# interlinkP1B.net
KiCad netlist of a schematic drawn in Altium Designer
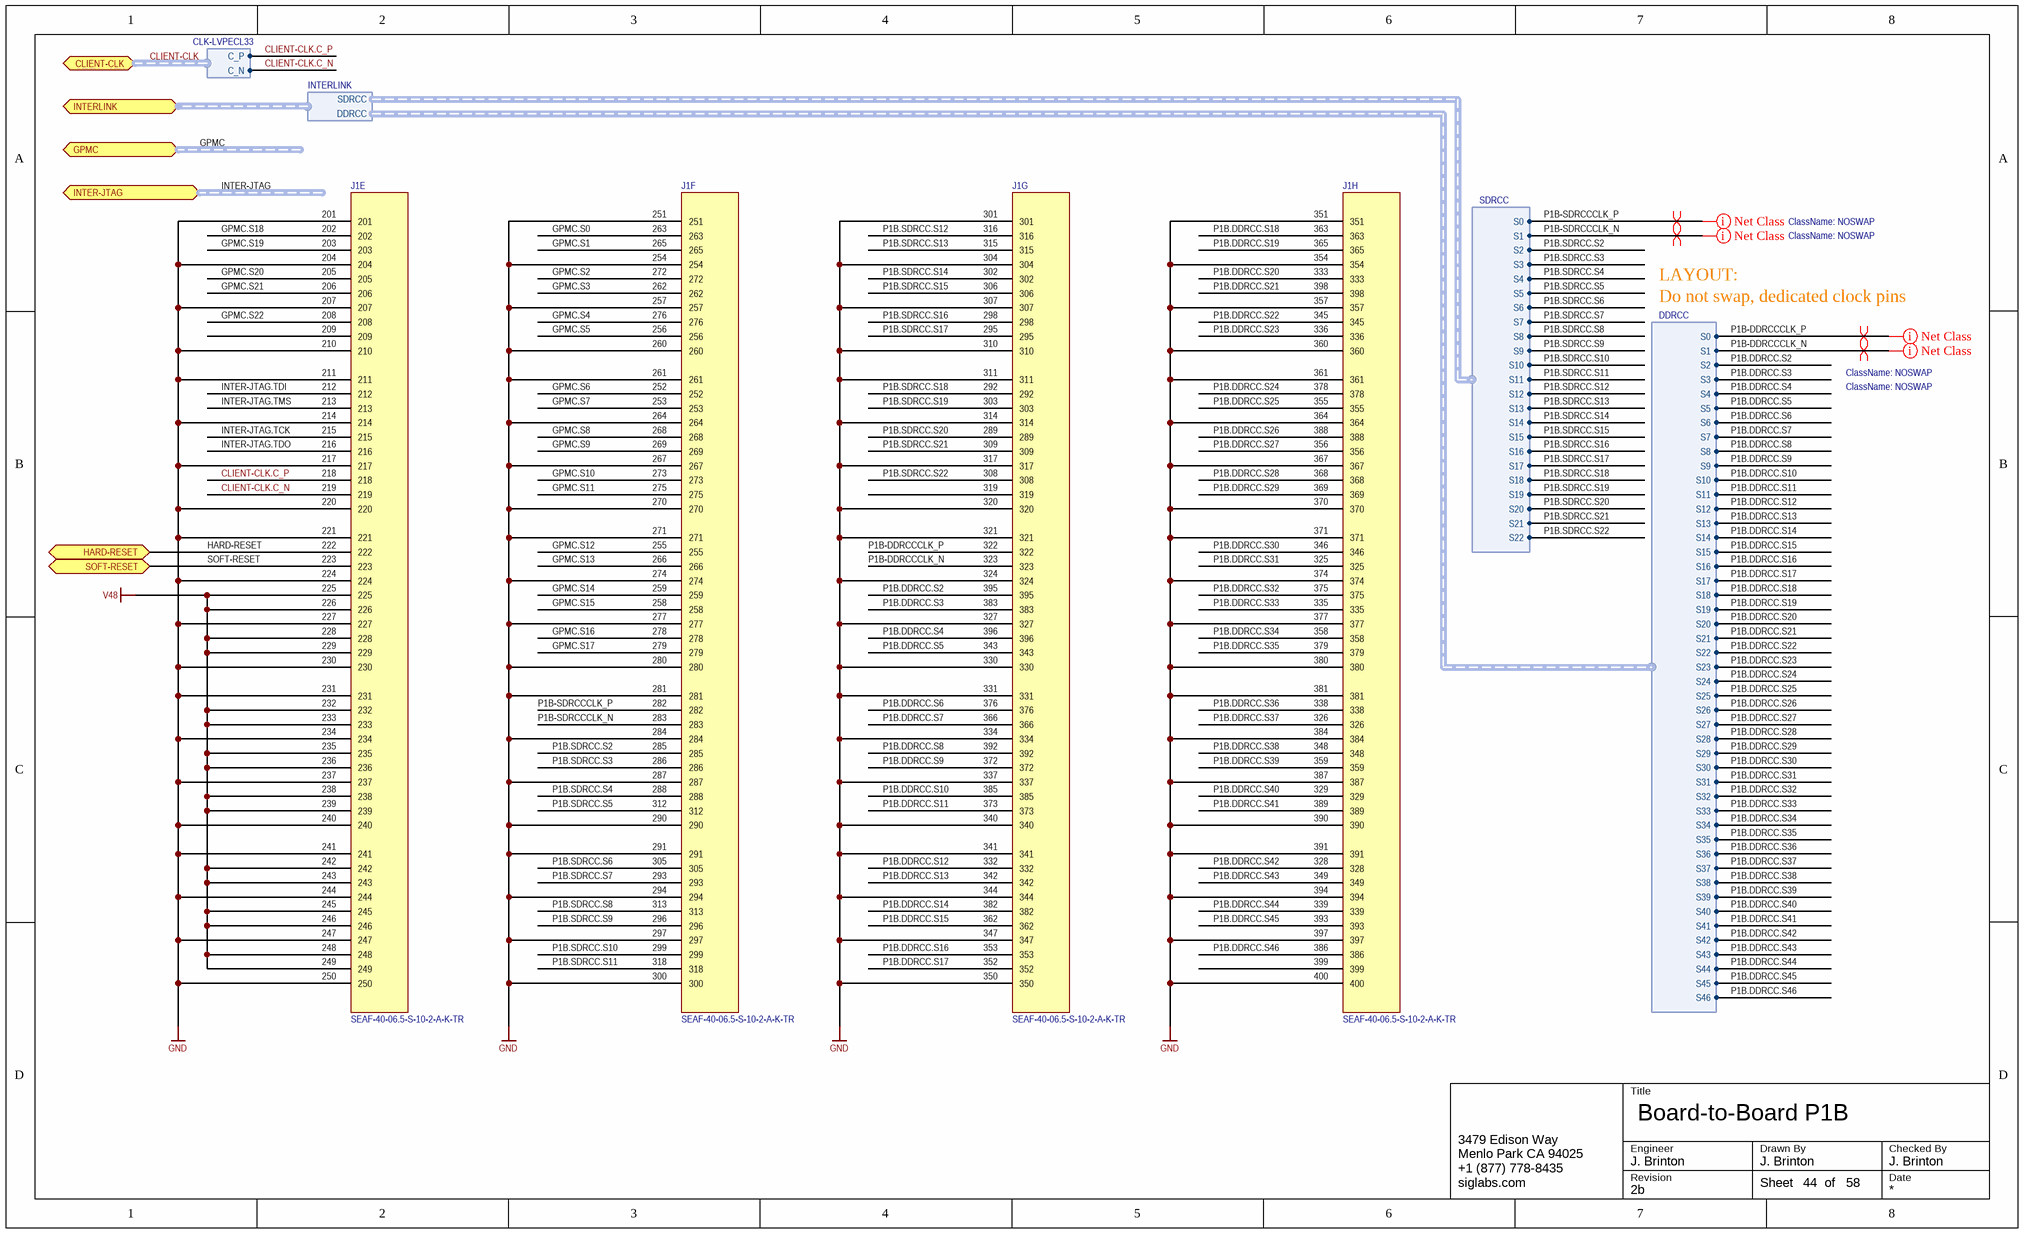
[diagram p0: interlinkP1B.SchDoc]

(export (version "E")
  (design (tool "Eeschema 10.0.6"))
  (components
    (comp (ref "J1")
      (value "SEAF-40-06.5-S-10-2-A-K-TR")
      (footprint "samtec:SEAF-40-06.5-S-10-2-A-K-TR")
      (description "Terminal Array Assembly, Surface Mount, 0.050\" Pitch, 400 Pins")
      (fields (field (name "MANUFACTURER") "Samtec"))
      (libsource (lib "") (part "SEAF-40-06.5-S-10-2-A-K-TR_1"))
    )
  )
  (nets
    (net (code "7") (name "/CLIENT-CLK.C_N") (class "Default")
      (node (ref "J1") (pin "219") (pinfunction "219_219") (pintype "passive"))
    )
    (net (code "8") (name "/CLIENT-CLK.C_P") (class "Default")
      (node (ref "J1") (pin "218") (pinfunction "218_218") (pintype "passive"))
    )
    (net (code "10") (name "/GPMC.S0") (class "Default")
      (node (ref "J1") (pin "263") (pinfunction "263_263") (pintype "passive"))
    )
    (net (code "11") (name "/GPMC.S1") (class "Default")
      (node (ref "J1") (pin "265") (pinfunction "265_265") (pintype "passive"))
    )
    (net (code "12") (name "/GPMC.S2") (class "Default")
      (node (ref "J1") (pin "272") (pinfunction "272_272") (pintype "passive"))
    )
    (net (code "13") (name "/GPMC.S3") (class "Default")
      (node (ref "J1") (pin "262") (pinfunction "262_262") (pintype "passive"))
    )
    (net (code "14") (name "/GPMC.S4") (class "Default")
      (node (ref "J1") (pin "276") (pinfunction "276_276") (pintype "passive"))
    )
    (net (code "15") (name "/GPMC.S5") (class "Default")
      (node (ref "J1") (pin "256") (pinfunction "256_256") (pintype "passive"))
    )
    (net (code "16") (name "/GPMC.S6") (class "Default")
      (node (ref "J1") (pin "252") (pinfunction "252_252") (pintype "passive"))
    )
    (net (code "17") (name "/GPMC.S7") (class "Default")
      (node (ref "J1") (pin "253") (pinfunction "253_253") (pintype "passive"))
    )
    (net (code "18") (name "/GPMC.S8") (class "Default")
      (node (ref "J1") (pin "268") (pinfunction "268_268") (pintype "passive"))
    )
    (net (code "19") (name "/GPMC.S9") (class "Default")
      (node (ref "J1") (pin "269") (pinfunction "269_269") (pintype "passive"))
    )
    (net (code "20") (name "/GPMC.S10") (class "Default")
      (node (ref "J1") (pin "273") (pinfunction "273_273") (pintype "passive"))
    )
    (net (code "21") (name "/GPMC.S11") (class "Default")
      (node (ref "J1") (pin "275") (pinfunction "275_275") (pintype "passive"))
    )
    (net (code "22") (name "/GPMC.S12") (class "Default")
      (node (ref "J1") (pin "255") (pinfunction "255_255") (pintype "passive"))
    )
    (net (code "23") (name "/GPMC.S13") (class "Default")
      (node (ref "J1") (pin "266") (pinfunction "266_266") (pintype "passive"))
    )
    (net (code "24") (name "/GPMC.S14") (class "Default")
      (node (ref "J1") (pin "259") (pinfunction "259_259") (pintype "passive"))
    )
    (net (code "25") (name "/GPMC.S15") (class "Default")
      (node (ref "J1") (pin "258") (pinfunction "258_258") (pintype "passive"))
    )
    (net (code "26") (name "/GPMC.S16") (class "Default")
      (node (ref "J1") (pin "278") (pinfunction "278_278") (pintype "passive"))
    )
    (net (code "27") (name "/GPMC.S17") (class "Default")
      (node (ref "J1") (pin "279") (pinfunction "279_279") (pintype "passive"))
    )
    (net (code "28") (name "/GPMC.S18") (class "Default")
      (node (ref "J1") (pin "202") (pinfunction "202_202") (pintype "passive"))
    )
    (net (code "29") (name "/GPMC.S19") (class "Default")
      (node (ref "J1") (pin "203") (pinfunction "203_203") (pintype "passive"))
    )
    (net (code "30") (name "/GPMC.S20") (class "Default")
      (node (ref "J1") (pin "205") (pinfunction "205_205") (pintype "passive"))
    )
    (net (code "31") (name "/GPMC.S21") (class "Default")
      (node (ref "J1") (pin "206") (pinfunction "206_206") (pintype "passive"))
    )
    (net (code "32") (name "/GPMC.S22") (class "Default")
      (node (ref "J1") (pin "208") (pinfunction "208_208") (pintype "passive"))
    )
    (net (code "33") (name "/HARD-RESET") (class "Default")
      (node (ref "J1") (pin "222") (pinfunction "222_222") (pintype "passive"))
    )
    (net (code "34") (name "/INTER-JTAG.TCK") (class "Default")
      (node (ref "J1") (pin "215") (pinfunction "215_215") (pintype "passive"))
    )
    (net (code "35") (name "/INTER-JTAG.TDI") (class "Default")
      (node (ref "J1") (pin "212") (pinfunction "212_212") (pintype "passive"))
    )
    (net (code "36") (name "/INTER-JTAG.TDO") (class "Default")
      (node (ref "J1") (pin "216") (pinfunction "216_216") (pintype "passive"))
    )
    (net (code "37") (name "/INTER-JTAG.TMS") (class "Default")
      (node (ref "J1") (pin "213") (pinfunction "213_213") (pintype "passive"))
    )
    (net (code "39") (name "/P1B-DDRCCCLK_N") (class "Default")
      (node (ref "J1") (pin "323") (pinfunction "323_323") (pintype "passive"))
    )
    (net (code "40") (name "/P1B-DDRCCCLK_P") (class "Default")
      (node (ref "J1") (pin "322") (pinfunction "322_322") (pintype "passive"))
    )
    (net (code "41") (name "/P1B-SDRCCCLK_N") (class "Default")
      (node (ref "J1") (pin "283") (pinfunction "283_283") (pintype "passive"))
    )
    (net (code "42") (name "/P1B-SDRCCCLK_P") (class "Default")
      (node (ref "J1") (pin "282") (pinfunction "282_282") (pintype "passive"))
    )
    (net (code "43") (name "/P1B.DDRCC.S2") (class "Default")
      (node (ref "J1") (pin "395") (pinfunction "395_395") (pintype "passive"))
    )
    (net (code "44") (name "/P1B.DDRCC.S3") (class "Default")
      (node (ref "J1") (pin "383") (pinfunction "383_383") (pintype "passive"))
    )
    (net (code "45") (name "/P1B.DDRCC.S4") (class "Default")
      (node (ref "J1") (pin "396") (pinfunction "396_396") (pintype "passive"))
    )
    (net (code "46") (name "/P1B.DDRCC.S5") (class "Default")
      (node (ref "J1") (pin "343") (pinfunction "343_343") (pintype "passive"))
    )
    (net (code "47") (name "/P1B.DDRCC.S6") (class "Default")
      (node (ref "J1") (pin "376") (pinfunction "376_376") (pintype "passive"))
    )
    (net (code "48") (name "/P1B.DDRCC.S7") (class "Default")
      (node (ref "J1") (pin "366") (pinfunction "366_366") (pintype "passive"))
    )
    (net (code "49") (name "/P1B.DDRCC.S8") (class "Default")
      (node (ref "J1") (pin "392") (pinfunction "392_392") (pintype "passive"))
    )
    (net (code "50") (name "/P1B.DDRCC.S9") (class "Default")
      (node (ref "J1") (pin "372") (pinfunction "372_372") (pintype "passive"))
    )
    (net (code "51") (name "/P1B.DDRCC.S10") (class "Default")
      (node (ref "J1") (pin "385") (pinfunction "385_385") (pintype "passive"))
    )
    (net (code "52") (name "/P1B.DDRCC.S11") (class "Default")
      (node (ref "J1") (pin "373") (pinfunction "373_373") (pintype "passive"))
    )
    (net (code "53") (name "/P1B.DDRCC.S12") (class "Default")
      (node (ref "J1") (pin "332") (pinfunction "332_332") (pintype "passive"))
    )
    (net (code "54") (name "/P1B.DDRCC.S13") (class "Default")
      (node (ref "J1") (pin "342") (pinfunction "342_342") (pintype "passive"))
    )
    (net (code "55") (name "/P1B.DDRCC.S14") (class "Default")
      (node (ref "J1") (pin "382") (pinfunction "382_382") (pintype "passive"))
    )
    (net (code "56") (name "/P1B.DDRCC.S15") (class "Default")
      (node (ref "J1") (pin "362") (pinfunction "362_362") (pintype "passive"))
    )
    (net (code "57") (name "/P1B.DDRCC.S16") (class "Default")
      (node (ref "J1") (pin "353") (pinfunction "353_353") (pintype "passive"))
    )
    (net (code "58") (name "/P1B.DDRCC.S17") (class "Default")
      (node (ref "J1") (pin "352") (pinfunction "352_352") (pintype "passive"))
    )
    (net (code "59") (name "/P1B.DDRCC.S18") (class "Default")
      (node (ref "J1") (pin "363") (pinfunction "363_363") (pintype "passive"))
    )
    (net (code "60") (name "/P1B.DDRCC.S19") (class "Default")
      (node (ref "J1") (pin "365") (pinfunction "365_365") (pintype "passive"))
    )
    (net (code "61") (name "/P1B.DDRCC.S20") (class "Default")
      (node (ref "J1") (pin "333") (pinfunction "333_333") (pintype "passive"))
    )
    (net (code "62") (name "/P1B.DDRCC.S21") (class "Default")
      (node (ref "J1") (pin "398") (pinfunction "398_398") (pintype "passive"))
    )
    (net (code "63") (name "/P1B.DDRCC.S22") (class "Default")
      (node (ref "J1") (pin "345") (pinfunction "345_345") (pintype "passive"))
    )
    (net (code "64") (name "/P1B.DDRCC.S23") (class "Default")
      (node (ref "J1") (pin "336") (pinfunction "336_336") (pintype "passive"))
    )
    (net (code "65") (name "/P1B.DDRCC.S24") (class "Default")
      (node (ref "J1") (pin "378") (pinfunction "378_378") (pintype "passive"))
    )
    (net (code "66") (name "/P1B.DDRCC.S25") (class "Default")
      (node (ref "J1") (pin "355") (pinfunction "355_355") (pintype "passive"))
    )
    (net (code "67") (name "/P1B.DDRCC.S26") (class "Default")
      (node (ref "J1") (pin "388") (pinfunction "388_388") (pintype "passive"))
    )
    (net (code "68") (name "/P1B.DDRCC.S27") (class "Default")
      (node (ref "J1") (pin "356") (pinfunction "356_356") (pintype "passive"))
    )
    (net (code "69") (name "/P1B.DDRCC.S28") (class "Default")
      (node (ref "J1") (pin "368") (pinfunction "368_368") (pintype "passive"))
    )
    (net (code "70") (name "/P1B.DDRCC.S29") (class "Default")
      (node (ref "J1") (pin "369") (pinfunction "369_369") (pintype "passive"))
    )
    (net (code "71") (name "/P1B.DDRCC.S30") (class "Default")
      (node (ref "J1") (pin "346") (pinfunction "346_346") (pintype "passive"))
    )
    (net (code "72") (name "/P1B.DDRCC.S31") (class "Default")
      (node (ref "J1") (pin "325") (pinfunction "325_325") (pintype "passive"))
    )
    (net (code "73") (name "/P1B.DDRCC.S32") (class "Default")
      (node (ref "J1") (pin "375") (pinfunction "375_375") (pintype "passive"))
    )
    (net (code "74") (name "/P1B.DDRCC.S33") (class "Default")
      (node (ref "J1") (pin "335") (pinfunction "335_335") (pintype "passive"))
    )
    (net (code "75") (name "/P1B.DDRCC.S34") (class "Default")
      (node (ref "J1") (pin "358") (pinfunction "358_358") (pintype "passive"))
    )
    (net (code "76") (name "/P1B.DDRCC.S35") (class "Default")
      (node (ref "J1") (pin "379") (pinfunction "379_379") (pintype "passive"))
    )
    (net (code "77") (name "/P1B.DDRCC.S36") (class "Default")
      (node (ref "J1") (pin "338") (pinfunction "338_338") (pintype "passive"))
    )
    (net (code "78") (name "/P1B.DDRCC.S37") (class "Default")
      (node (ref "J1") (pin "326") (pinfunction "326_326") (pintype "passive"))
    )
    (net (code "79") (name "/P1B.DDRCC.S38") (class "Default")
      (node (ref "J1") (pin "348") (pinfunction "348_348") (pintype "passive"))
    )
    (net (code "80") (name "/P1B.DDRCC.S39") (class "Default")
      (node (ref "J1") (pin "359") (pinfunction "359_359") (pintype "passive"))
    )
    (net (code "81") (name "/P1B.DDRCC.S40") (class "Default")
      (node (ref "J1") (pin "329") (pinfunction "329_329") (pintype "passive"))
    )
    (net (code "82") (name "/P1B.DDRCC.S41") (class "Default")
      (node (ref "J1") (pin "389") (pinfunction "389_389") (pintype "passive"))
    )
    (net (code "83") (name "/P1B.DDRCC.S42") (class "Default")
      (node (ref "J1") (pin "328") (pinfunction "328_328") (pintype "passive"))
    )
    (net (code "84") (name "/P1B.DDRCC.S43") (class "Default")
      (node (ref "J1") (pin "349") (pinfunction "349_349") (pintype "passive"))
    )
    (net (code "85") (name "/P1B.DDRCC.S44") (class "Default")
      (node (ref "J1") (pin "339") (pinfunction "339_339") (pintype "passive"))
    )
    (net (code "86") (name "/P1B.DDRCC.S45") (class "Default")
      (node (ref "J1") (pin "393") (pinfunction "393_393") (pintype "passive"))
    )
    (net (code "87") (name "/P1B.DDRCC.S46") (class "Default")
      (node (ref "J1") (pin "386") (pinfunction "386_386") (pintype "passive"))
    )
    (net (code "88") (name "/P1B.SDRCC.S2") (class "Default")
      (node (ref "J1") (pin "285") (pinfunction "285_285") (pintype "passive"))
    )
    (net (code "89") (name "/P1B.SDRCC.S3") (class "Default")
      (node (ref "J1") (pin "286") (pinfunction "286_286") (pintype "passive"))
    )
    (net (code "90") (name "/P1B.SDRCC.S4") (class "Default")
      (node (ref "J1") (pin "288") (pinfunction "288_288") (pintype "passive"))
    )
    (net (code "91") (name "/P1B.SDRCC.S5") (class "Default")
      (node (ref "J1") (pin "312") (pinfunction "312_312") (pintype "passive"))
    )
    (net (code "92") (name "/P1B.SDRCC.S6") (class "Default")
      (node (ref "J1") (pin "305") (pinfunction "305_305") (pintype "passive"))
    )
    (net (code "93") (name "/P1B.SDRCC.S7") (class "Default")
      (node (ref "J1") (pin "293") (pinfunction "293_293") (pintype "passive"))
    )
    (net (code "94") (name "/P1B.SDRCC.S8") (class "Default")
      (node (ref "J1") (pin "313") (pinfunction "313_313") (pintype "passive"))
    )
    (net (code "95") (name "/P1B.SDRCC.S9") (class "Default")
      (node (ref "J1") (pin "296") (pinfunction "296_296") (pintype "passive"))
    )
    (net (code "96") (name "/P1B.SDRCC.S10") (class "Default")
      (node (ref "J1") (pin "299") (pinfunction "299_299") (pintype "passive"))
    )
    (net (code "97") (name "/P1B.SDRCC.S11") (class "Default")
      (node (ref "J1") (pin "318") (pinfunction "318_318") (pintype "passive"))
    )
    (net (code "98") (name "/P1B.SDRCC.S12") (class "Default")
      (node (ref "J1") (pin "316") (pinfunction "316_316") (pintype "passive"))
    )
    (net (code "99") (name "/P1B.SDRCC.S13") (class "Default")
      (node (ref "J1") (pin "315") (pinfunction "315_315") (pintype "passive"))
    )
    (net (code "100") (name "/P1B.SDRCC.S14") (class "Default")
      (node (ref "J1") (pin "302") (pinfunction "302_302") (pintype "passive"))
    )
    (net (code "101") (name "/P1B.SDRCC.S15") (class "Default")
      (node (ref "J1") (pin "306") (pinfunction "306_306") (pintype "passive"))
    )
    (net (code "102") (name "/P1B.SDRCC.S16") (class "Default")
      (node (ref "J1") (pin "298") (pinfunction "298_298") (pintype "passive"))
    )
    (net (code "103") (name "/P1B.SDRCC.S17") (class "Default")
      (node (ref "J1") (pin "295") (pinfunction "295_295") (pintype "passive"))
    )
    (net (code "104") (name "/P1B.SDRCC.S18") (class "Default")
      (node (ref "J1") (pin "292") (pinfunction "292_292") (pintype "passive"))
    )
    (net (code "105") (name "/P1B.SDRCC.S19") (class "Default")
      (node (ref "J1") (pin "303") (pinfunction "303_303") (pintype "passive"))
    )
    (net (code "106") (name "/P1B.SDRCC.S20") (class "Default")
      (node (ref "J1") (pin "289") (pinfunction "289_289") (pintype "passive"))
    )
    (net (code "107") (name "/P1B.SDRCC.S21") (class "Default")
      (node (ref "J1") (pin "309") (pinfunction "309_309") (pintype "passive"))
    )
    (net (code "108") (name "/P1B.SDRCC.S22") (class "Default")
      (node (ref "J1") (pin "308") (pinfunction "308_308") (pintype "passive"))
    )
    (net (code "109") (name "/SOFT-RESET") (class "Default")
      (node (ref "J1") (pin "223") (pinfunction "223_223") (pintype "passive"))
    )
    (net (code "114") (name "GND") (class "Default")
      (node (ref "J1") (pin "201") (pinfunction "201_201") (pintype "passive"))
      (node (ref "J1") (pin "204") (pinfunction "204_204") (pintype "passive"))
      (node (ref "J1") (pin "207") (pinfunction "207_207") (pintype "passive"))
      (node (ref "J1") (pin "210") (pinfunction "210_210") (pintype "passive"))
      (node (ref "J1") (pin "211") (pinfunction "211_211") (pintype "passive"))
      (node (ref "J1") (pin "214") (pinfunction "214_214") (pintype "passive"))
      (node (ref "J1") (pin "217") (pinfunction "217_217") (pintype "passive"))
      (node (ref "J1") (pin "220") (pinfunction "220_220") (pintype "passive"))
      (node (ref "J1") (pin "221") (pinfunction "221_221") (pintype "passive"))
      (node (ref "J1") (pin "224") (pinfunction "224_224") (pintype "passive"))
      (node (ref "J1") (pin "227") (pinfunction "227_227") (pintype "passive"))
      (node (ref "J1") (pin "230") (pinfunction "230_230") (pintype "passive"))
      (node (ref "J1") (pin "231") (pinfunction "231_231") (pintype "passive"))
      (node (ref "J1") (pin "234") (pinfunction "234_234") (pintype "passive"))
      (node (ref "J1") (pin "237") (pinfunction "237_237") (pintype "passive"))
      (node (ref "J1") (pin "240") (pinfunction "240_240") (pintype "passive"))
      (node (ref "J1") (pin "241") (pinfunction "241_241") (pintype "passive"))
      (node (ref "J1") (pin "244") (pinfunction "244_244") (pintype "passive"))
      (node (ref "J1") (pin "247") (pinfunction "247_247") (pintype "passive"))
      (node (ref "J1") (pin "250") (pinfunction "250_250") (pintype "passive"))
      (node (ref "J1") (pin "251") (pinfunction "251_251") (pintype "passive"))
      (node (ref "J1") (pin "254") (pinfunction "254_254") (pintype "passive"))
      (node (ref "J1") (pin "257") (pinfunction "257_257") (pintype "passive"))
      (node (ref "J1") (pin "260") (pinfunction "260_260") (pintype "passive"))
      (node (ref "J1") (pin "261") (pinfunction "261_261") (pintype "passive"))
      (node (ref "J1") (pin "264") (pinfunction "264_264") (pintype "passive"))
      (node (ref "J1") (pin "267") (pinfunction "267_267") (pintype "passive"))
      (node (ref "J1") (pin "270") (pinfunction "270_270") (pintype "passive"))
      (node (ref "J1") (pin "271") (pinfunction "271_271") (pintype "passive"))
      (node (ref "J1") (pin "274") (pinfunction "274_274") (pintype "passive"))
      (node (ref "J1") (pin "277") (pinfunction "277_277") (pintype "passive"))
      (node (ref "J1") (pin "280") (pinfunction "280_280") (pintype "passive"))
      (node (ref "J1") (pin "281") (pinfunction "281_281") (pintype "passive"))
      (node (ref "J1") (pin "284") (pinfunction "284_284") (pintype "passive"))
      (node (ref "J1") (pin "287") (pinfunction "287_287") (pintype "passive"))
      (node (ref "J1") (pin "290") (pinfunction "290_290") (pintype "passive"))
      (node (ref "J1") (pin "291") (pinfunction "291_291") (pintype "passive"))
      (node (ref "J1") (pin "294") (pinfunction "294_294") (pintype "passive"))
      (node (ref "J1") (pin "297") (pinfunction "297_297") (pintype "passive"))
      (node (ref "J1") (pin "300") (pinfunction "300_300") (pintype "passive"))
      (node (ref "J1") (pin "301") (pinfunction "301_301") (pintype "passive"))
      (node (ref "J1") (pin "304") (pinfunction "304_304") (pintype "passive"))
      (node (ref "J1") (pin "307") (pinfunction "307_307") (pintype "passive"))
      (node (ref "J1") (pin "310") (pinfunction "310_310") (pintype "passive"))
      (node (ref "J1") (pin "311") (pinfunction "311_311") (pintype "passive"))
      (node (ref "J1") (pin "314") (pinfunction "314_314") (pintype "passive"))
      (node (ref "J1") (pin "317") (pinfunction "317_317") (pintype "passive"))
      (node (ref "J1") (pin "320") (pinfunction "320_320") (pintype "passive"))
      (node (ref "J1") (pin "321") (pinfunction "321_321") (pintype "passive"))
      (node (ref "J1") (pin "324") (pinfunction "324_324") (pintype "passive"))
      (node (ref "J1") (pin "327") (pinfunction "327_327") (pintype "passive"))
      (node (ref "J1") (pin "330") (pinfunction "330_330") (pintype "passive"))
      (node (ref "J1") (pin "331") (pinfunction "331_331") (pintype "passive"))
      (node (ref "J1") (pin "334") (pinfunction "334_334") (pintype "passive"))
      (node (ref "J1") (pin "337") (pinfunction "337_337") (pintype "passive"))
      (node (ref "J1") (pin "340") (pinfunction "340_340") (pintype "passive"))
      (node (ref "J1") (pin "341") (pinfunction "341_341") (pintype "passive"))
      (node (ref "J1") (pin "344") (pinfunction "344_344") (pintype "passive"))
      (node (ref "J1") (pin "347") (pinfunction "347_347") (pintype "passive"))
      (node (ref "J1") (pin "350") (pinfunction "350_350") (pintype "passive"))
      (node (ref "J1") (pin "351") (pinfunction "351_351") (pintype "passive"))
      (node (ref "J1") (pin "354") (pinfunction "354_354") (pintype "passive"))
      (node (ref "J1") (pin "357") (pinfunction "357_357") (pintype "passive"))
      (node (ref "J1") (pin "360") (pinfunction "360_360") (pintype "passive"))
      (node (ref "J1") (pin "361") (pinfunction "361_361") (pintype "passive"))
      (node (ref "J1") (pin "364") (pinfunction "364_364") (pintype "passive"))
      (node (ref "J1") (pin "367") (pinfunction "367_367") (pintype "passive"))
      (node (ref "J1") (pin "370") (pinfunction "370_370") (pintype "passive"))
      (node (ref "J1") (pin "371") (pinfunction "371_371") (pintype "passive"))
      (node (ref "J1") (pin "374") (pinfunction "374_374") (pintype "passive"))
      (node (ref "J1") (pin "377") (pinfunction "377_377") (pintype "passive"))
      (node (ref "J1") (pin "380") (pinfunction "380_380") (pintype "passive"))
      (node (ref "J1") (pin "381") (pinfunction "381_381") (pintype "passive"))
      (node (ref "J1") (pin "384") (pinfunction "384_384") (pintype "passive"))
      (node (ref "J1") (pin "387") (pinfunction "387_387") (pintype "passive"))
      (node (ref "J1") (pin "390") (pinfunction "390_390") (pintype "passive"))
      (node (ref "J1") (pin "391") (pinfunction "391_391") (pintype "passive"))
      (node (ref "J1") (pin "394") (pinfunction "394_394") (pintype "passive"))
      (node (ref "J1") (pin "397") (pinfunction "397_397") (pintype "passive"))
      (node (ref "J1") (pin "400") (pinfunction "400_400") (pintype "passive"))
    )
    (net (code "115") (name "V48") (class "Default")
      (node (ref "J1") (pin "225") (pinfunction "225_225") (pintype "passive"))
      (node (ref "J1") (pin "226") (pinfunction "226_226") (pintype "passive"))
      (node (ref "J1") (pin "228") (pinfunction "228_228") (pintype "passive"))
      (node (ref "J1") (pin "229") (pinfunction "229_229") (pintype "passive"))
      (node (ref "J1") (pin "232") (pinfunction "232_232") (pintype "passive"))
      (node (ref "J1") (pin "233") (pinfunction "233_233") (pintype "passive"))
      (node (ref "J1") (pin "235") (pinfunction "235_235") (pintype "passive"))
      (node (ref "J1") (pin "236") (pinfunction "236_236") (pintype "passive"))
      (node (ref "J1") (pin "238") (pinfunction "238_238") (pintype "passive"))
      (node (ref "J1") (pin "239") (pinfunction "239_239") (pintype "passive"))
      (node (ref "J1") (pin "242") (pinfunction "242_242") (pintype "passive"))
      (node (ref "J1") (pin "243") (pinfunction "243_243") (pintype "passive"))
      (node (ref "J1") (pin "245") (pinfunction "245_245") (pintype "passive"))
      (node (ref "J1") (pin "246") (pinfunction "246_246") (pintype "passive"))
      (node (ref "J1") (pin "248") (pinfunction "248_248") (pintype "passive"))
      (node (ref "J1") (pin "249") (pinfunction "249_249") (pintype "passive"))
    )
    (net (code "116") (name "unconnected-(J1-Pad209)") (class "Default")
      (node (ref "J1") (pin "209") (pinfunction "209_209") (pintype "passive"))
    )
    (net (code "117") (name "unconnected-(J1-Pad319)") (class "Default")
      (node (ref "J1") (pin "319") (pinfunction "319_319") (pintype "passive"))
    )
    (net (code "118") (name "unconnected-(J1-Pad399)") (class "Default")
      (node (ref "J1") (pin "399") (pinfunction "399_399") (pintype "passive"))
    )
  )
)
